# Power_Board_5V.net
KiCad netlist of a schematic drawn in Altium Designer
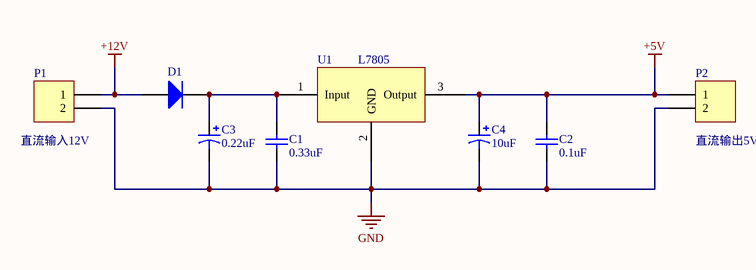
[diagram p0: Power_Board_5V.SchDoc]

(export (version "E")
  (design (tool "Eeschema 10.0.6"))
  (components
    (comp (ref "C1")
      (value "0.33uF")
      (footprint "RAD-0.3")
      (description "Capacitor")
      (fields (field (name "Comment") "Cap") (field (name "PUBLISHER") "Altium Limited"))
      (libsource (lib "Miscellaneous Devices") (part "Cap"))
    )
    (comp (ref "C2")
      (value "0.1uF")
      (footprint "RAD-0.3")
      (description "Capacitor")
      (fields (field (name "Comment") "Cap") (field (name "PUBLISHER") "Altium Limited"))
      (libsource (lib "Miscellaneous Devices") (part "Cap"))
    )
    (comp (ref "C3")
      (value "0.22uF")
      (footprint "RB7.6-15")
      (description "Polarized Capacitor (Radial)")
      (fields (field (name "Comment") "Cap Pol1") (field (name "PUBLISHER") "Altium Limited"))
      (libsource (lib "Miscellaneous Devices") (part "Cap Pol1"))
    )
    (comp (ref "C4")
      (value "10uF")
      (footprint "RB7.6-15")
      (description "Polarized Capacitor (Radial)")
      (fields (field (name "Comment") "Cap Pol1") (field (name "PUBLISHER") "Altium Limited"))
      (libsource (lib "Miscellaneous Devices") (part "Cap Pol1"))
    )
    (comp (ref "D1")
      (value "Diode")
      (footprint "SMC")
      (description "Default Diode")
      (fields (field (name "PUBLISHER") "Altium Limited"))
      (libsource (lib "Miscellaneous Devices") (part "Diode"))
    )
    (comp (ref "P1")
      (value "Header 2")
      (footprint "HDR1X2")
      (description "Header, 2-Pin")
      (fields (field (name "PUBLISHER") "Altium Limited"))
      (libsource (lib "") (part "Header 2_1"))
    )
    (comp (ref "P2")
      (value "Header 2")
      (footprint "HDR1X2")
      (description "Header, 2-Pin")
      (fields (field (name "PUBLISHER") "Altium Limited"))
      (libsource (lib "Miscellaneous Connectors") (part "Header 2"))
    )
    (comp (ref "U1") (value "L7805") (libsource (lib "Yi Ping_Schlib") (part "L7805")))
  )
  (nets
    (net (code "1") (name "+5V") (class "Default")
      (node (ref "C2") (pin "2") (pinfunction "2_2") (pintype "passive"))
      (node (ref "C4") (pin "1") (pinfunction "1_1") (pintype "passive"))
      (node (ref "P2") (pin "1") (pinfunction "1_1") (pintype "passive"))
      (node (ref "U1") (pin "3") (pinfunction "Output_3") (pintype "passive"))
    )
    (net (code "2") (name "+12V") (class "Default")
      (node (ref "D1") (pin "1") (pinfunction "A_1") (pintype "passive"))
      (node (ref "P1") (pin "1") (pinfunction "1_1") (pintype "passive"))
    )
    (net (code "3") (name "GND") (class "Default")
      (node (ref "C1") (pin "1") (pinfunction "1_1") (pintype "passive"))
      (node (ref "C2") (pin "1") (pinfunction "1_1") (pintype "passive"))
      (node (ref "C3") (pin "2") (pinfunction "2_2") (pintype "passive"))
      (node (ref "C4") (pin "2") (pinfunction "2_2") (pintype "passive"))
      (node (ref "P1") (pin "2") (pinfunction "2_2") (pintype "passive"))
      (node (ref "P2") (pin "2") (pinfunction "2_2") (pintype "passive"))
      (node (ref "U1") (pin "2") (pinfunction "GND_2") (pintype "passive"))
    )
    (net (code "4") (name "Net-(D1-K)") (class "Default")
      (node (ref "C1") (pin "2") (pinfunction "2_2") (pintype "passive"))
      (node (ref "C3") (pin "1") (pinfunction "1_1") (pintype "passive"))
      (node (ref "D1") (pin "2") (pinfunction "K_2") (pintype "passive"))
      (node (ref "U1") (pin "1") (pinfunction "Input_1") (pintype "passive"))
    )
  )
)
